# eDNA_Sampler.net
KiCad netlist of a schematic drawn in EAGLE
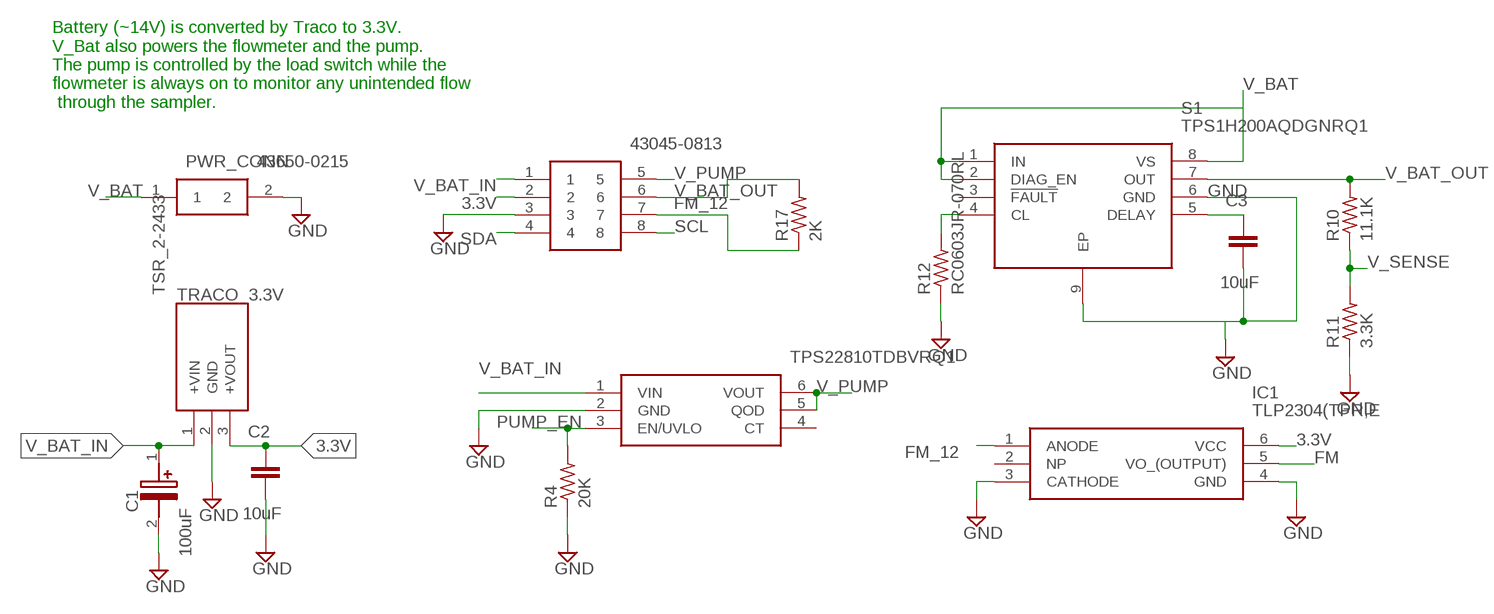
[diagram p0: schematic, sheet 1]
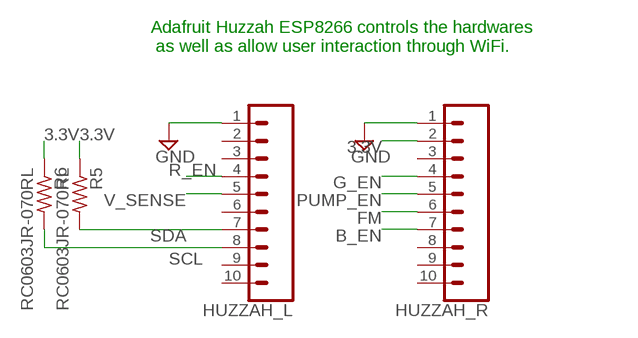
[diagram p1: schematic, sheet 2]
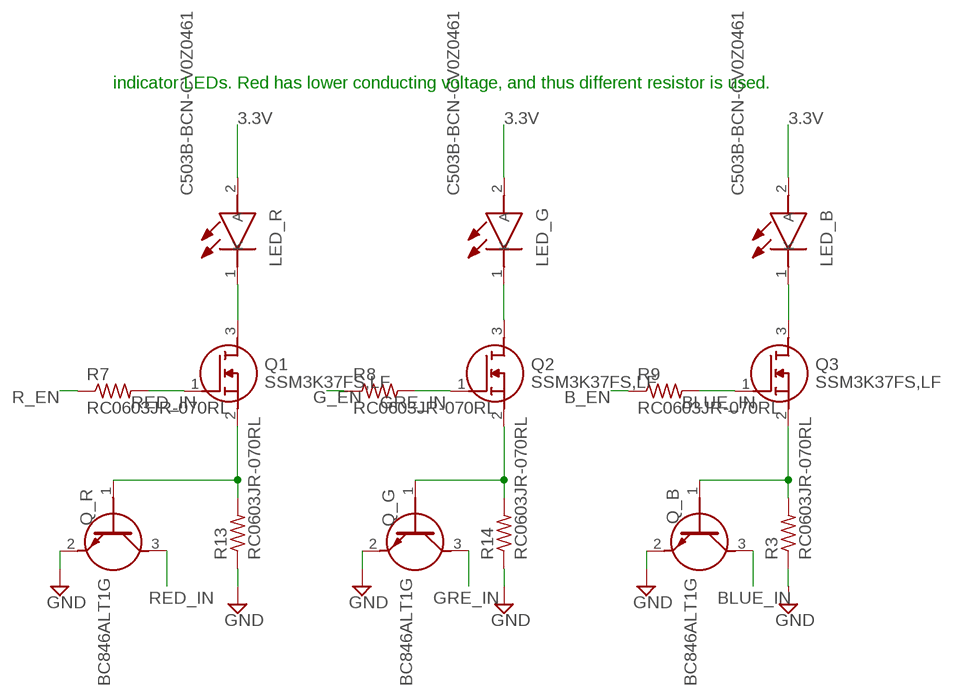
[diagram p2: schematic, sheet 3]
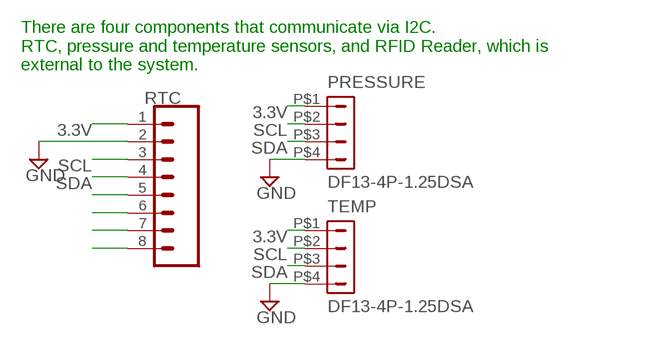
[diagram p3: schematic, sheet 4]

(export (version "E")
  (design (tool "Eeschema 10.0.6"))
  (components
    (comp (ref "PRESSURE")
      (value "DF13-4P-1.25DSA")
      (footprint "eagle-import:DF13-4P-1.25DSA")
      (libsource (lib "eagle-import") (part "DF13-4P-1.25DSA"))
    )
    (comp (ref "RTC")
      (value "CONN_08\"")
      (footprint "eagle-import:1X08")
      (libsource (lib "eagle-import") (part "CONN_08{dblquote}"))
    )
    (comp (ref "TEMP")
      (value "DF13-4P-1.25DSA")
      (footprint "eagle-import:DF13-4P-1.25DSA")
      (libsource (lib "eagle-import") (part "DF13-4P-1.25DSA"))
    )
    (comp (ref "C1")
      (value "100uF")
      (footprint "eagle-import:CAPPRD250W50D680H1250")
      (fields
        (field (name "MANUFACTURER_PART_NUMBER") "35ZLH100MEFC6.3X11")
        (field (name "MOUSER_PART_NUMBER") "232-35ZLH100MEFC63X1")
      )
      (libsource (lib "eagle-import") (part "35ZLH100MEFC6.3X11"))
    )
    (comp (ref "C2")
      (value "10uF")
      (footprint "eagle-import:CAP_0603")
      (fields
        (field (name "DIGIKEY_PART_NUMBER") "399-7814-2-ND")
        (field (name "MANUFACTURER") "KEMET")
        (field (name "MPN") "C0603C100C5GACTU")
        (field (name "CREATED_BY") "PCBLayout.com")
      )
      (libsource (lib "eagle-import") (part "C0603C100C5GACTU"))
    )
    (comp (ref "C3")
      (value "10uF")
      (footprint "eagle-import:CAP_0603")
      (fields
        (field (name "DIGIKEY_PART_NUMBER") "399-7814-2-ND")
        (field (name "MANUFACTURER") "KEMET")
        (field (name "MPN") "C0603C100C5GACTU")
        (field (name "CREATED_BY") "PCBLayout.com")
      )
      (libsource (lib "eagle-import") (part "C0603C100C5GACTU"))
    )
    (comp (ref "IC1")
      (value "TLP2304(TPR,E")
      (footprint "eagle-import:SOIC127P700X230-6N")
      (fields (field (name "MOUSER_PART_NUMBER") "757-TLP2304TPRE"))
      (libsource (lib "eagle-import") (part "TLP2304(TPR,E"))
    )
    (comp (ref "LOAD_SWITCH")
      (value "TPS22810TDBVRQ1")
      (footprint "eagle-import:SOT95P280X145-6N")
      (fields (field (name "MOUSER_PART_NUMBER") "595-TPS22810TDBVRQ1"))
      (libsource (lib "eagle-import") (part "TPS22810TDBVRQ1"))
    )
    (comp (ref "PENETRATOR_CONN")
      (value "43045-0813")
      (footprint "eagle-import:43045-0813")
      (fields (field (name "MOUSER_PART_NUMBER") "538-43045-0813"))
      (libsource (lib "eagle-import") (part "43045-0813"))
    )
    (comp (ref "PWR_CONN")
      (value "43650-0215")
      (footprint "eagle-import:43650-0217")
      (fields (field (name "MOUSER_PART_NUMBER") "538-43650-0215"))
      (libsource (lib "eagle-import") (part "43650-0215"))
    )
    (comp (ref "R4")
      (value "20K")
      (footprint "eagle-import:RES_0603")
      (fields
        (field (name "DIGIKEY_PART_NUMBER") "311-0.0GRTR-ND")
        (field (name "MANUFACTURER") "Yageo")
        (field (name "MPN") "RC0603JR-070RL")
        (field (name "CREATED_BY") "PCBLayout.com")
      )
      (libsource (lib "eagle-import") (part "RC0603JR-070RL"))
    )
    (comp (ref "R10")
      (value "11.1K")
      (footprint "eagle-import:RES_0603")
      (fields
        (field (name "DIGIKEY_PART_NUMBER") "311-0.0GRTR-ND")
        (field (name "MANUFACTURER") "Yageo")
        (field (name "MPN") "RC0603JR-070RL")
        (field (name "CREATED_BY") "PCBLayout.com")
      )
      (libsource (lib "eagle-import") (part "RC0603JR-070RL"))
    )
    (comp (ref "R11")
      (value "3.3K")
      (footprint "eagle-import:RES_0603")
      (fields
        (field (name "DIGIKEY_PART_NUMBER") "311-0.0GRTR-ND")
        (field (name "MANUFACTURER") "Yageo")
        (field (name "MPN") "RC0603JR-070RL")
        (field (name "CREATED_BY") "PCBLayout.com")
      )
      (libsource (lib "eagle-import") (part "RC0603JR-070RL"))
    )
    (comp (ref "R12")
      (value "RC0603JR-070RL")
      (footprint "eagle-import:RES_0603")
      (fields
        (field (name "DIGIKEY_PART_NUMBER") "311-0.0GRTR-ND")
        (field (name "MANUFACTURER") "Yageo")
        (field (name "CREATED_BY") "PCBLayout.com")
      )
      (libsource (lib "eagle-import") (part "RC0603JR-070RL"))
    )
    (comp (ref "R17")
      (value "2K")
      (footprint "eagle-import:RES_0603")
      (fields
        (field (name "DIGIKEY_PART_NUMBER") "311-0.0GRTR-ND")
        (field (name "MANUFACTURER") "Yageo")
        (field (name "MPN") "RC0603JR-070RL")
        (field (name "CREATED_BY") "PCBLayout.com")
      )
      (libsource (lib "eagle-import") (part "RC0603JR-070RL"))
    )
    (comp (ref "S1")
      (value "TPS1H200AQDGNRQ1")
      (footprint "eagle-import:SOP65P490X110-9N")
      (fields (field (name "MOUSER_PART_NUMBER") "595-TPS1H200AQDGNRQ1"))
      (libsource (lib "eagle-import") (part "TPS1H200AQDGNRQ1"))
    )
    (comp (ref "TRACO_3.3V")
      (value "TSR_2-2433")
      (footprint "eagle-import:TSR-2")
      (fields
        (field (name "MANUFACTURER_PART_NUMBER") "TSR 2-2433")
        (field (name "MOUSER_PART_NUMBER") "495-TSR2-2433")
      )
      (libsource (lib "eagle-import") (part "TSR_2-2433"))
    )
    (comp (ref "LED_B")
      (value "C503B-BCN-CV0Z0461")
      (footprint "eagle-import:C503B-BCN")
      (fields (field (name "MOUSER_PART_NUMBER") "941-C503BBCNCV0Z0461"))
      (libsource (lib "eagle-import") (part "C503B-BCN-CV0Z0461"))
    )
    (comp (ref "LED_G")
      (value "C503B-BCN-CV0Z0461")
      (footprint "eagle-import:C503B-BCN")
      (fields (field (name "MOUSER_PART_NUMBER") "941-C503BBCNCV0Z0461"))
      (libsource (lib "eagle-import") (part "C503B-BCN-CV0Z0461"))
    )
    (comp (ref "LED_R")
      (value "C503B-BCN-CV0Z0461")
      (footprint "eagle-import:C503B-BCN")
      (fields (field (name "MOUSER_PART_NUMBER") "941-C503BBCNCV0Z0461"))
      (libsource (lib "eagle-import") (part "C503B-BCN-CV0Z0461"))
    )
    (comp (ref "Q1")
      (value "SSM3K37FS,LF")
      (footprint "eagle-import:SSM3K37FSLF")
      (fields (field (name "MOUSER_PART_NUMBER") "757-SSM3K37FSLF"))
      (libsource (lib "eagle-import") (part "SSM3K37FS,LF"))
    )
    (comp (ref "Q2")
      (value "SSM3K37FS,LF")
      (footprint "eagle-import:SSM3K37FSLF")
      (fields (field (name "MOUSER_PART_NUMBER") "757-SSM3K37FSLF"))
      (libsource (lib "eagle-import") (part "SSM3K37FS,LF"))
    )
    (comp (ref "Q3")
      (value "SSM3K37FS,LF")
      (footprint "eagle-import:SSM3K37FSLF")
      (fields (field (name "MOUSER_PART_NUMBER") "757-SSM3K37FSLF"))
      (libsource (lib "eagle-import") (part "SSM3K37FS,LF"))
    )
    (comp (ref "Q_B")
      (value "BC846ALT1G")
      (footprint "eagle-import:SOT95P237X111-3N")
      (fields (field (name "MOUSER_PART_NUMBER") "863-BC846ALT1G"))
      (libsource (lib "eagle-import") (part "BC846ALT1G"))
    )
    (comp (ref "Q_G")
      (value "BC846ALT1G")
      (footprint "eagle-import:SOT95P237X111-3N")
      (fields (field (name "MOUSER_PART_NUMBER") "863-BC846ALT1G"))
      (libsource (lib "eagle-import") (part "BC846ALT1G"))
    )
    (comp (ref "Q_R")
      (value "BC846ALT1G")
      (footprint "eagle-import:SOT95P237X111-3N")
      (fields (field (name "MOUSER_PART_NUMBER") "863-BC846ALT1G"))
      (libsource (lib "eagle-import") (part "BC846ALT1G"))
    )
    (comp (ref "R3")
      (value "RC0603JR-070RL")
      (footprint "eagle-import:RES_0603")
      (fields
        (field (name "DIGIKEY_PART_NUMBER") "311-0.0GRTR-ND")
        (field (name "MANUFACTURER") "Yageo")
        (field (name "CREATED_BY") "PCBLayout.com")
      )
      (libsource (lib "eagle-import") (part "RC0603JR-070RL"))
    )
    (comp (ref "R7")
      (value "RC0603JR-070RL")
      (footprint "eagle-import:RES_0603")
      (fields
        (field (name "DIGIKEY_PART_NUMBER") "311-0.0GRTR-ND")
        (field (name "MANUFACTURER") "Yageo")
        (field (name "CREATED_BY") "PCBLayout.com")
      )
      (libsource (lib "eagle-import") (part "RC0603JR-070RL"))
    )
    (comp (ref "R8")
      (value "RC0603JR-070RL")
      (footprint "eagle-import:RES_0603")
      (fields
        (field (name "DIGIKEY_PART_NUMBER") "311-0.0GRTR-ND")
        (field (name "MANUFACTURER") "Yageo")
        (field (name "CREATED_BY") "PCBLayout.com")
      )
      (libsource (lib "eagle-import") (part "RC0603JR-070RL"))
    )
    (comp (ref "R9")
      (value "RC0603JR-070RL")
      (footprint "eagle-import:RES_0603")
      (fields
        (field (name "DIGIKEY_PART_NUMBER") "311-0.0GRTR-ND")
        (field (name "MANUFACTURER") "Yageo")
        (field (name "CREATED_BY") "PCBLayout.com")
      )
      (libsource (lib "eagle-import") (part "RC0603JR-070RL"))
    )
    (comp (ref "R13")
      (value "RC0603JR-070RL")
      (footprint "eagle-import:RES_0603")
      (fields
        (field (name "DIGIKEY_PART_NUMBER") "311-0.0GRTR-ND")
        (field (name "MANUFACTURER") "Yageo")
        (field (name "CREATED_BY") "PCBLayout.com")
      )
      (libsource (lib "eagle-import") (part "RC0603JR-070RL"))
    )
    (comp (ref "R14")
      (value "RC0603JR-070RL")
      (footprint "eagle-import:RES_0603")
      (fields
        (field (name "DIGIKEY_PART_NUMBER") "311-0.0GRTR-ND")
        (field (name "MANUFACTURER") "Yageo")
        (field (name "CREATED_BY") "PCBLayout.com")
      )
      (libsource (lib "eagle-import") (part "RC0603JR-070RL"))
    )
    (comp (ref "HUZZAH_L")
      (value "CONN_10\"")
      (footprint "eagle-import:1X10")
      (libsource (lib "eagle-import") (part "CONN_10{dblquote}"))
    )
    (comp (ref "HUZZAH_R")
      (value "CONN_10\"")
      (footprint "eagle-import:1X10")
      (libsource (lib "eagle-import") (part "CONN_10{dblquote}"))
    )
    (comp (ref "R5")
      (value "RC0603JR-070RL")
      (footprint "eagle-import:RES_0603")
      (fields
        (field (name "DIGIKEY_PART_NUMBER") "311-0.0GRTR-ND")
        (field (name "MANUFACTURER") "Yageo")
        (field (name "CREATED_BY") "PCBLayout.com")
      )
      (libsource (lib "eagle-import") (part "RC0603JR-070RL"))
    )
    (comp (ref "R6")
      (value "RC0603JR-070RL")
      (footprint "eagle-import:RES_0603")
      (fields
        (field (name "DIGIKEY_PART_NUMBER") "311-0.0GRTR-ND")
        (field (name "MANUFACTURER") "Yageo")
        (field (name "CREATED_BY") "PCBLayout.com")
      )
      (libsource (lib "eagle-import") (part "RC0603JR-070RL"))
    )
  )
  (nets
    (net (code "1") (name "3.3V") (class "Default")
      (node (ref "C2") (pin "1") (pinfunction "1_1") (pintype "passive"))
      (node (ref "HUZZAH_R") (pin "2") (pinfunction "2_2") (pintype "passive"))
      (node (ref "IC1") (pin "6") (pinfunction "VCC_6") (pintype "bidirectional"))
      (node (ref "LED_B") (pin "2") (pinfunction "A_2") (pintype "bidirectional"))
      (node (ref "LED_G") (pin "2") (pinfunction "A_2") (pintype "bidirectional"))
      (node (ref "LED_R") (pin "2") (pinfunction "A_2") (pintype "bidirectional"))
      (node (ref "PENETRATOR_CONN") (pin "2") (pinfunction "2_2") (pintype "bidirectional"))
      (node (ref "PRESSURE") (pin "P$1") (pinfunction "1_P$1") (pintype "passive"))
      (node (ref "R5") (pin "1") (pinfunction "1_1") (pintype "passive"))
      (node (ref "R6") (pin "1") (pinfunction "1_1") (pintype "passive"))
      (node (ref "RTC") (pin "1") (pinfunction "1_1") (pintype "passive"))
      (node (ref "TEMP") (pin "P$1") (pinfunction "1_P$1") (pintype "passive"))
      (node (ref "TRACO_3.3V") (pin "3") (pinfunction "+VOUT_3") (pintype "bidirectional"))
    )
    (net (code "2") (name "BLUE_IN") (class "Default")
      (node (ref "Q3") (pin "1") (pinfunction "G_1") (pintype "input"))
      (node (ref "Q_B") (pin "3") (pinfunction "C_3") (pintype "bidirectional"))
      (node (ref "R9") (pin "2") (pinfunction "2_2") (pintype "passive"))
    )
    (net (code "3") (name "B_EN") (class "Default")
      (node (ref "HUZZAH_R") (pin "7") (pinfunction "7_7") (pintype "passive"))
      (node (ref "R9") (pin "1") (pinfunction "1_1") (pintype "passive"))
    )
    (net (code "4") (name "FM") (class "Default")
      (node (ref "HUZZAH_R") (pin "6") (pinfunction "6_6") (pintype "passive"))
      (node (ref "IC1") (pin "5") (pinfunction "VO_(OUTPUT)_5") (pintype "bidirectional"))
    )
    (net (code "5") (name "FM_12") (class "Default")
      (node (ref "IC1") (pin "1") (pinfunction "ANODE_1") (pintype "bidirectional"))
      (node (ref "PENETRATOR_CONN") (pin "7") (pinfunction "7_7") (pintype "bidirectional"))
      (node (ref "R17") (pin "1") (pinfunction "1_1") (pintype "passive"))
    )
    (net (code "6") (name "GND") (class "Default")
      (node (ref "C1") (pin "2") (pinfunction "-_2") (pintype "bidirectional"))
      (node (ref "C2") (pin "2") (pinfunction "2_2") (pintype "passive"))
      (node (ref "C3") (pin "2") (pinfunction "2_2") (pintype "passive"))
      (node (ref "HUZZAH_L") (pin "1") (pinfunction "1_1") (pintype "passive"))
      (node (ref "HUZZAH_R") (pin "1") (pinfunction "1_1") (pintype "passive"))
      (node (ref "IC1") (pin "3") (pinfunction "CATHODE_3") (pintype "bidirectional"))
      (node (ref "IC1") (pin "4") (pinfunction "GND_4") (pintype "bidirectional"))
      (node (ref "LOAD_SWITCH") (pin "2") (pinfunction "GND_2") (pintype "bidirectional"))
      (node (ref "PENETRATOR_CONN") (pin "3") (pinfunction "3_3") (pintype "bidirectional"))
      (node (ref "PRESSURE") (pin "P$4") (pinfunction "4_P$4") (pintype "passive"))
      (node (ref "PWR_CONN") (pin "2") (pinfunction "2_2") (pintype "bidirectional"))
      (node (ref "Q_B") (pin "2") (pinfunction "E_2") (pintype "bidirectional"))
      (node (ref "Q_G") (pin "2") (pinfunction "E_2") (pintype "bidirectional"))
      (node (ref "Q_R") (pin "2") (pinfunction "E_2") (pintype "bidirectional"))
      (node (ref "R11") (pin "1") (pinfunction "1_1") (pintype "passive"))
      (node (ref "R12") (pin "1") (pinfunction "1_1") (pintype "passive"))
      (node (ref "R13") (pin "1") (pinfunction "1_1") (pintype "passive"))
      (node (ref "R14") (pin "1") (pinfunction "1_1") (pintype "passive"))
      (node (ref "R3") (pin "1") (pinfunction "1_1") (pintype "passive"))
      (node (ref "R4") (pin "1") (pinfunction "1_1") (pintype "passive"))
      (node (ref "RTC") (pin "2") (pinfunction "2_2") (pintype "passive"))
      (node (ref "S1") (pin "6") (pinfunction "GND_6") (pintype "bidirectional"))
      (node (ref "S1") (pin "9") (pinfunction "EP_9") (pintype "bidirectional"))
      (node (ref "TEMP") (pin "P$4") (pinfunction "4_P$4") (pintype "passive"))
      (node (ref "TRACO_3.3V") (pin "2") (pinfunction "GND_2") (pintype "bidirectional"))
    )
    (net (code "7") (name "GRE_IN") (class "Default")
      (node (ref "Q2") (pin "1") (pinfunction "G_1") (pintype "input"))
      (node (ref "Q_G") (pin "3") (pinfunction "C_3") (pintype "bidirectional"))
      (node (ref "R8") (pin "2") (pinfunction "2_2") (pintype "passive"))
    )
    (net (code "8") (name "G_EN") (class "Default")
      (node (ref "HUZZAH_R") (pin "4") (pinfunction "4_4") (pintype "passive"))
      (node (ref "R8") (pin "1") (pinfunction "1_1") (pintype "passive"))
    )
    (net (code "9") (name "Net-(LED_B-K)") (class "Default")
      (node (ref "LED_B") (pin "1") (pinfunction "K_1") (pintype "bidirectional"))
      (node (ref "Q3") (pin "3") (pinfunction "D_3") (pintype "output"))
    )
    (net (code "10") (name "Net-(LED_G-K)") (class "Default")
      (node (ref "LED_G") (pin "1") (pinfunction "K_1") (pintype "bidirectional"))
      (node (ref "Q2") (pin "3") (pinfunction "D_3") (pintype "output"))
    )
    (net (code "11") (name "Net-(LED_R-K)") (class "Default")
      (node (ref "LED_R") (pin "1") (pinfunction "K_1") (pintype "bidirectional"))
      (node (ref "Q1") (pin "3") (pinfunction "D_3") (pintype "output"))
    )
    (net (code "12") (name "Net-(Q1-S)") (class "Default")
      (node (ref "Q1") (pin "2") (pinfunction "S_2") (pintype "input"))
      (node (ref "Q_R") (pin "1") (pinfunction "B_1") (pintype "bidirectional"))
      (node (ref "R13") (pin "2") (pinfunction "2_2") (pintype "passive"))
    )
    (net (code "13") (name "Net-(Q2-S)") (class "Default")
      (node (ref "Q2") (pin "2") (pinfunction "S_2") (pintype "input"))
      (node (ref "Q_G") (pin "1") (pinfunction "B_1") (pintype "bidirectional"))
      (node (ref "R14") (pin "2") (pinfunction "2_2") (pintype "passive"))
    )
    (net (code "14") (name "Net-(Q3-S)") (class "Default")
      (node (ref "Q3") (pin "2") (pinfunction "S_2") (pintype "input"))
      (node (ref "Q_B") (pin "1") (pinfunction "B_1") (pintype "bidirectional"))
      (node (ref "R3") (pin "2") (pinfunction "2_2") (pintype "passive"))
    )
    (net (code "15") (name "Net-(S1-CL)") (class "Default")
      (node (ref "R12") (pin "2") (pinfunction "2_2") (pintype "passive"))
      (node (ref "S1") (pin "4") (pinfunction "CL_4") (pintype "bidirectional"))
    )
    (net (code "16") (name "Net-(S1-DELAY)") (class "Default")
      (node (ref "C3") (pin "1") (pinfunction "1_1") (pintype "passive"))
      (node (ref "S1") (pin "5") (pinfunction "DELAY_5") (pintype "bidirectional"))
    )
    (net (code "17") (name "PUMP_EN") (class "Default")
      (node (ref "HUZZAH_R") (pin "5") (pinfunction "5_5") (pintype "passive"))
      (node (ref "LOAD_SWITCH") (pin "3") (pinfunction "EN/UVLO_3") (pintype "bidirectional"))
      (node (ref "R4") (pin "2") (pinfunction "2_2") (pintype "passive"))
    )
    (net (code "18") (name "RED_IN") (class "Default")
      (node (ref "Q1") (pin "1") (pinfunction "G_1") (pintype "input"))
      (node (ref "Q_R") (pin "3") (pinfunction "C_3") (pintype "bidirectional"))
      (node (ref "R7") (pin "2") (pinfunction "2_2") (pintype "passive"))
    )
    (net (code "19") (name "R_EN") (class "Default")
      (node (ref "HUZZAH_L") (pin "4") (pinfunction "4_4") (pintype "passive"))
      (node (ref "R7") (pin "1") (pinfunction "1_1") (pintype "passive"))
    )
    (net (code "20") (name "SCL") (class "Default")
      (node (ref "HUZZAH_L") (pin "8") (pinfunction "8_8") (pintype "passive"))
      (node (ref "PENETRATOR_CONN") (pin "8") (pinfunction "8_8") (pintype "bidirectional"))
      (node (ref "PRESSURE") (pin "P$2") (pinfunction "2_P$2") (pintype "passive"))
      (node (ref "R6") (pin "2") (pinfunction "2_2") (pintype "passive"))
      (node (ref "RTC") (pin "3") (pinfunction "3_3") (pintype "passive"))
      (node (ref "TEMP") (pin "P$2") (pinfunction "2_P$2") (pintype "passive"))
    )
    (net (code "21") (name "SDA") (class "Default")
      (node (ref "HUZZAH_L") (pin "7") (pinfunction "7_7") (pintype "passive"))
      (node (ref "PENETRATOR_CONN") (pin "4") (pinfunction "4_4") (pintype "bidirectional"))
      (node (ref "PRESSURE") (pin "P$3") (pinfunction "3_P$3") (pintype "passive"))
      (node (ref "R5") (pin "2") (pinfunction "2_2") (pintype "passive"))
      (node (ref "RTC") (pin "4") (pinfunction "4_4") (pintype "passive"))
      (node (ref "TEMP") (pin "P$3") (pinfunction "3_P$3") (pintype "passive"))
    )
    (net (code "22") (name "V_BAT") (class "Default")
      (node (ref "PWR_CONN") (pin "1") (pinfunction "1_1") (pintype "bidirectional"))
      (node (ref "S1") (pin "1") (pinfunction "IN_1") (pintype "bidirectional"))
      (node (ref "S1") (pin "2") (pinfunction "DIAG_EN_2") (pintype "bidirectional"))
      (node (ref "S1") (pin "8") (pinfunction "VS_8") (pintype "bidirectional"))
    )
    (net (code "23") (name "V_BAT_IN") (class "Default")
      (node (ref "C1") (pin "1") (pinfunction "+_1") (pintype "bidirectional"))
      (node (ref "LOAD_SWITCH") (pin "1") (pinfunction "VIN_1") (pintype "bidirectional"))
      (node (ref "PENETRATOR_CONN") (pin "1") (pinfunction "1_1") (pintype "bidirectional"))
      (node (ref "TRACO_3.3V") (pin "1") (pinfunction "+VIN_1") (pintype "bidirectional"))
    )
    (net (code "24") (name "V_BAT_OUT") (class "Default")
      (node (ref "PENETRATOR_CONN") (pin "6") (pinfunction "6_6") (pintype "bidirectional"))
      (node (ref "R10") (pin "2") (pinfunction "2_2") (pintype "passive"))
      (node (ref "R17") (pin "2") (pinfunction "2_2") (pintype "passive"))
      (node (ref "S1") (pin "7") (pinfunction "OUT_7") (pintype "bidirectional"))
    )
    (net (code "25") (name "V_PUMP") (class "Default")
      (node (ref "LOAD_SWITCH") (pin "5") (pinfunction "QOD_5") (pintype "bidirectional"))
      (node (ref "LOAD_SWITCH") (pin "6") (pinfunction "VOUT_6") (pintype "bidirectional"))
      (node (ref "PENETRATOR_CONN") (pin "5") (pinfunction "5_5") (pintype "bidirectional"))
    )
    (net (code "26") (name "V_SENSE") (class "Default")
      (node (ref "HUZZAH_L") (pin "5") (pinfunction "5_5") (pintype "passive"))
      (node (ref "R10") (pin "1") (pinfunction "1_1") (pintype "passive"))
      (node (ref "R11") (pin "2") (pinfunction "2_2") (pintype "passive"))
    )
    (net (code "27") (name "unconnected-(HUZZAH_L-Pad2)") (class "Default")
      (node (ref "HUZZAH_L") (pin "2") (pinfunction "2_2") (pintype "passive"))
    )
    (net (code "28") (name "unconnected-(HUZZAH_L-Pad3)") (class "Default")
      (node (ref "HUZZAH_L") (pin "3") (pinfunction "3_3") (pintype "passive"))
    )
    (net (code "29") (name "unconnected-(HUZZAH_L-Pad6)") (class "Default")
      (node (ref "HUZZAH_L") (pin "6") (pinfunction "6_6") (pintype "passive"))
    )
    (net (code "30") (name "unconnected-(HUZZAH_L-Pad9)") (class "Default")
      (node (ref "HUZZAH_L") (pin "9") (pinfunction "9_9") (pintype "passive"))
    )
    (net (code "31") (name "unconnected-(HUZZAH_L-Pad10)") (class "Default")
      (node (ref "HUZZAH_L") (pin "10") (pinfunction "10_10") (pintype "passive"))
    )
    (net (code "32") (name "unconnected-(HUZZAH_R-Pad3)") (class "Default")
      (node (ref "HUZZAH_R") (pin "3") (pinfunction "3_3") (pintype "passive"))
    )
    (net (code "33") (name "unconnected-(HUZZAH_R-Pad8)") (class "Default")
      (node (ref "HUZZAH_R") (pin "8") (pinfunction "8_8") (pintype "passive"))
    )
    (net (code "34") (name "unconnected-(HUZZAH_R-Pad9)") (class "Default")
      (node (ref "HUZZAH_R") (pin "9") (pinfunction "9_9") (pintype "passive"))
    )
    (net (code "35") (name "unconnected-(HUZZAH_R-Pad10)") (class "Default")
      (node (ref "HUZZAH_R") (pin "10") (pinfunction "10_10") (pintype "passive"))
    )
    (net (code "36") (name "unconnected-(IC1-NP-Pad2)") (class "Default")
      (node (ref "IC1") (pin "2") (pinfunction "NP_2") (pintype "bidirectional"))
    )
    (net (code "37") (name "unconnected-(LOAD_SWITCH-CT-Pad4)") (class "Default")
      (node (ref "LOAD_SWITCH") (pin "4") (pinfunction "CT_4") (pintype "bidirectional"))
    )
    (net (code "38") (name "unconnected-(RTC-Pad5)") (class "Default")
      (node (ref "RTC") (pin "5") (pinfunction "5_5") (pintype "passive"))
    )
    (net (code "39") (name "unconnected-(RTC-Pad6)") (class "Default")
      (node (ref "RTC") (pin "6") (pinfunction "6_6") (pintype "passive"))
    )
    (net (code "40") (name "unconnected-(RTC-Pad7)") (class "Default")
      (node (ref "RTC") (pin "7") (pinfunction "7_7") (pintype "passive"))
    )
    (net (code "41") (name "unconnected-(RTC-Pad8)") (class "Default")
      (node (ref "RTC") (pin "8") (pinfunction "8_8") (pintype "passive"))
    )
    (net (code "42") (name "unconnected-(S1-~{FAULT}-Pad3)") (class "Default")
      (node (ref "S1") (pin "3") (pinfunction "~{FAULT}_3") (pintype "bidirectional"))
    )
  )
)
